# mcp23007_uln2803a.net
KiCad netlist of a schematic drawn in EAGLE
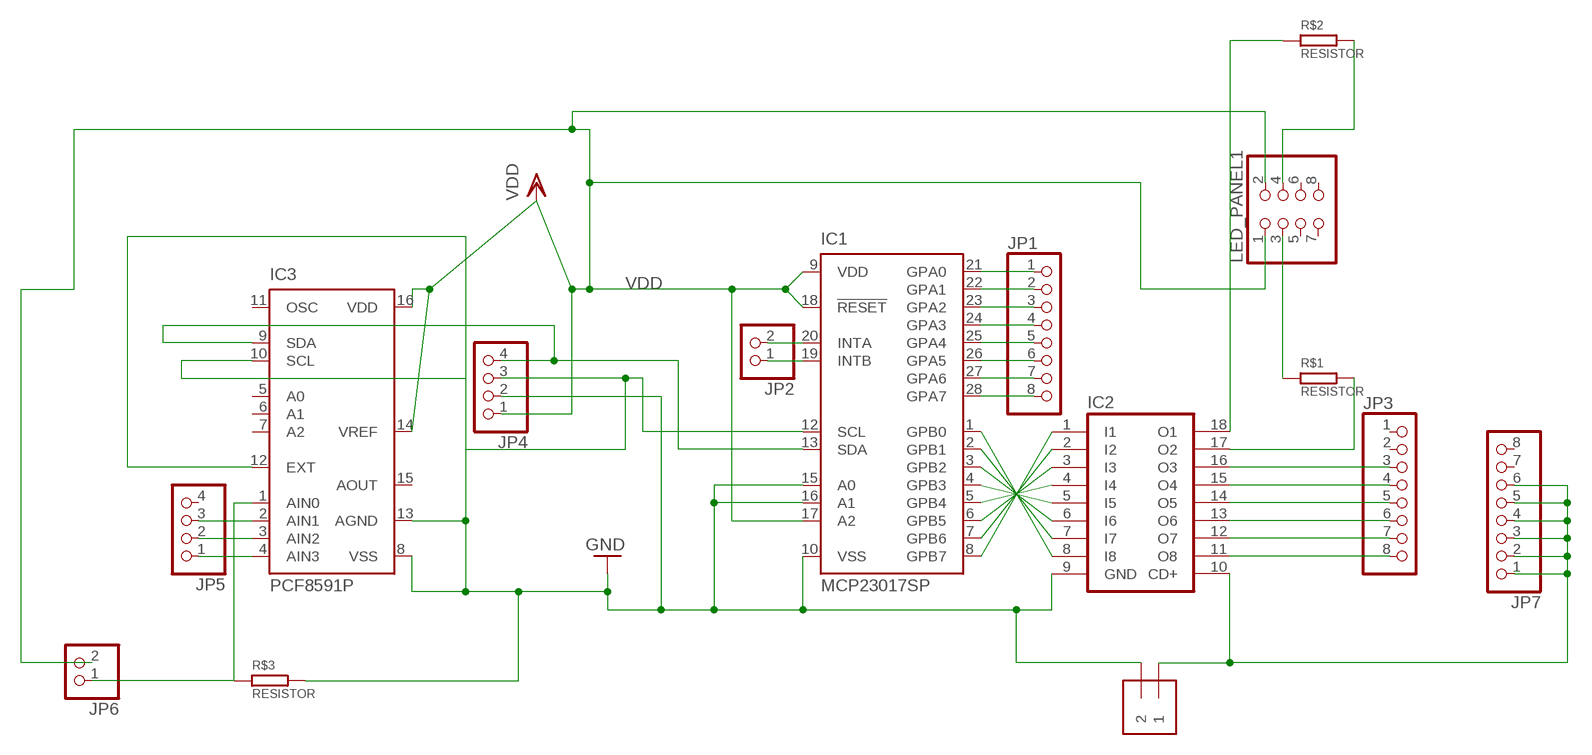
[diagram p0: schematic, sheet 1]

(export (version "E")
  (design (tool "Eeschema 10.0.6"))
  (components
    (comp (ref "IC1")
      (value "MCP23017SP")
      (footprint "eagle-import:DIL28-3")
      (fields (field (name "MF") "MICROCHIP") (field (name "MPN") "MCP23017-E/SP"))
      (libsource (lib "eagle-import") (part "MCP23017SP"))
    )
    (comp (ref "IC2")
      (value "ULN2803A")
      (footprint "eagle-import:DIL18")
      (libsource (lib "eagle-import") (part "ULN2803A"))
    )
    (comp (ref "IC3")
      (value "PCF8591P")
      (footprint "eagle-import:DIL16")
      (fields (field (name "MF") "FARNELL"))
      (libsource (lib "eagle-import") (part "PCF8591P"))
    )
    (comp (ref "JP1")
      (value "PINHD-1X8")
      (footprint "eagle-import:1X08")
      (libsource (lib "eagle-import") (part "PINHD-1X8"))
    )
    (comp (ref "JP2")
      (value "PINHD-1X2")
      (footprint "eagle-import:1X02")
      (libsource (lib "eagle-import") (part "PINHD-1X2"))
    )
    (comp (ref "JP3")
      (value "PINHD-1X8")
      (footprint "eagle-import:1X08")
      (libsource (lib "eagle-import") (part "PINHD-1X8"))
    )
    (comp (ref "JP4")
      (value "PINHD-1X4")
      (footprint "eagle-import:1X04")
      (libsource (lib "eagle-import") (part "PINHD-1X4"))
    )
    (comp (ref "JP5")
      (value "PINHD-1X4")
      (footprint "eagle-import:1X04")
      (libsource (lib "eagle-import") (part "PINHD-1X4"))
    )
    (comp (ref "JP6")
      (value "PINHD-1X2")
      (footprint "eagle-import:1X02")
      (libsource (lib "eagle-import") (part "PINHD-1X2"))
    )
    (comp (ref "JP7")
      (value "PINHD-1X8")
      (footprint "eagle-import:1X08")
      (libsource (lib "eagle-import") (part "PINHD-1X8"))
    )
    (comp (ref "LED_PANEL1")
      (value "PINHD-2X4")
      (footprint "eagle-import:2X04")
      (libsource (lib "eagle-import") (part "PINHD-2X4"))
    )
    (comp (ref "R$1")
      (value "RESISTOR")
      (footprint "eagle-import:RESISTOR_1_4")
      (libsource (lib "eagle-import") (part "RESISTOR"))
    )
    (comp (ref "R$2")
      (value "RESISTOR")
      (footprint "eagle-import:RESISTOR_1_4")
      (libsource (lib "eagle-import") (part "RESISTOR"))
    )
    (comp (ref "R$3")
      (value "RESISTOR")
      (footprint "eagle-import:RESISTOR_1_4")
      (libsource (lib "eagle-import") (part "RESISTOR"))
    )
    (comp (ref "VCC")
      (value "1X2-3.5MM")
      (footprint "eagle-import:1X2-3.5MM")
      (libsource (lib "eagle-import") (part "1X2-3.5MM"))
    )
  )
  (nets
    (net (code "1") (name "GND") (class "Default")
      (node (ref "IC1") (pin "10") (pinfunction "VSS_10") (pintype "power_in"))
      (node (ref "IC1") (pin "15") (pinfunction "A0_15") (pintype "input"))
      (node (ref "IC1") (pin "16") (pinfunction "A1_16") (pintype "input"))
      (node (ref "IC2") (pin "9") (pinfunction "GND_9") (pintype "power_in"))
      (node (ref "IC3") (pin "12") (pinfunction "EXT_12") (pintype "input"))
      (node (ref "IC3") (pin "13") (pinfunction "AGND_13") (pintype "power_in"))
      (node (ref "IC3") (pin "8") (pinfunction "VSS_8") (pintype "power_in"))
      (node (ref "JP4") (pin "2") (pinfunction "2_2") (pintype "passive"))
      (node (ref "R$3") (pin "P$1") (pinfunction "P$1_P$1") (pintype "passive"))
      (node (ref "VCC") (pin "2") (pinfunction "2_2") (pintype "passive"))
    )
    (net (code "2") (name "Net-(IC1-GPA0)") (class "Default")
      (node (ref "IC1") (pin "21") (pinfunction "GPA0_21") (pintype "bidirectional"))
      (node (ref "JP1") (pin "1") (pinfunction "1_1") (pintype "passive"))
    )
    (net (code "3") (name "Net-(IC1-GPA1)") (class "Default")
      (node (ref "IC1") (pin "22") (pinfunction "GPA1_22") (pintype "bidirectional"))
      (node (ref "JP1") (pin "2") (pinfunction "2_2") (pintype "passive"))
    )
    (net (code "4") (name "Net-(IC1-GPA2)") (class "Default")
      (node (ref "IC1") (pin "23") (pinfunction "GPA2_23") (pintype "bidirectional"))
      (node (ref "JP1") (pin "3") (pinfunction "3_3") (pintype "passive"))
    )
    (net (code "5") (name "Net-(IC1-GPA3)") (class "Default")
      (node (ref "IC1") (pin "24") (pinfunction "GPA3_24") (pintype "bidirectional"))
      (node (ref "JP1") (pin "4") (pinfunction "4_4") (pintype "passive"))
    )
    (net (code "6") (name "Net-(IC1-GPA4)") (class "Default")
      (node (ref "IC1") (pin "25") (pinfunction "GPA4_25") (pintype "bidirectional"))
      (node (ref "JP1") (pin "5") (pinfunction "5_5") (pintype "passive"))
    )
    (net (code "7") (name "Net-(IC1-GPA5)") (class "Default")
      (node (ref "IC1") (pin "26") (pinfunction "GPA5_26") (pintype "bidirectional"))
      (node (ref "JP1") (pin "6") (pinfunction "6_6") (pintype "passive"))
    )
    (net (code "8") (name "Net-(IC1-GPA6)") (class "Default")
      (node (ref "IC1") (pin "27") (pinfunction "GPA6_27") (pintype "bidirectional"))
      (node (ref "JP1") (pin "7") (pinfunction "7_7") (pintype "passive"))
    )
    (net (code "9") (name "Net-(IC1-GPA7)") (class "Default")
      (node (ref "IC1") (pin "28") (pinfunction "GPA7_28") (pintype "bidirectional"))
      (node (ref "JP1") (pin "8") (pinfunction "8_8") (pintype "passive"))
    )
    (net (code "10") (name "Net-(IC1-GPB0)") (class "Default")
      (node (ref "IC1") (pin "1") (pinfunction "GPB0_1") (pintype "bidirectional"))
      (node (ref "IC2") (pin "8") (pinfunction "I8_8") (pintype "input"))
    )
    (net (code "11") (name "Net-(IC1-GPB1)") (class "Default")
      (node (ref "IC1") (pin "2") (pinfunction "GPB1_2") (pintype "bidirectional"))
      (node (ref "IC2") (pin "7") (pinfunction "I7_7") (pintype "input"))
    )
    (net (code "12") (name "Net-(IC1-GPB2)") (class "Default")
      (node (ref "IC1") (pin "3") (pinfunction "GPB2_3") (pintype "bidirectional"))
      (node (ref "IC2") (pin "6") (pinfunction "I6_6") (pintype "input"))
    )
    (net (code "13") (name "Net-(IC1-GPB3)") (class "Default")
      (node (ref "IC1") (pin "4") (pinfunction "GPB3_4") (pintype "bidirectional"))
      (node (ref "IC2") (pin "5") (pinfunction "I5_5") (pintype "input"))
    )
    (net (code "14") (name "Net-(IC1-GPB4)") (class "Default")
      (node (ref "IC1") (pin "5") (pinfunction "GPB4_5") (pintype "bidirectional"))
      (node (ref "IC2") (pin "4") (pinfunction "I4_4") (pintype "input"))
    )
    (net (code "15") (name "Net-(IC1-GPB5)") (class "Default")
      (node (ref "IC1") (pin "6") (pinfunction "GPB5_6") (pintype "bidirectional"))
      (node (ref "IC2") (pin "3") (pinfunction "I3_3") (pintype "input"))
    )
    (net (code "16") (name "Net-(IC1-GPB6)") (class "Default")
      (node (ref "IC1") (pin "7") (pinfunction "GPB6_7") (pintype "bidirectional"))
      (node (ref "IC2") (pin "2") (pinfunction "I2_2") (pintype "input"))
    )
    (net (code "17") (name "Net-(IC1-GPB7)") (class "Default")
      (node (ref "IC1") (pin "8") (pinfunction "GPB7_8") (pintype "bidirectional"))
      (node (ref "IC2") (pin "1") (pinfunction "I1_1") (pintype "input"))
    )
    (net (code "18") (name "Net-(IC1-INTA)") (class "Default")
      (node (ref "IC1") (pin "20") (pinfunction "INTA_20") (pintype "output"))
      (node (ref "JP2") (pin "2") (pinfunction "2_2") (pintype "passive"))
    )
    (net (code "19") (name "Net-(IC1-INTB)") (class "Default")
      (node (ref "IC1") (pin "19") (pinfunction "INTB_19") (pintype "output"))
      (node (ref "JP2") (pin "1") (pinfunction "1_1") (pintype "passive"))
    )
    (net (code "20") (name "Net-(IC1-SCL)") (class "Default")
      (node (ref "IC1") (pin "12") (pinfunction "SCL_12") (pintype "input"))
      (node (ref "IC3") (pin "10") (pinfunction "SCL_10") (pintype "input"))
      (node (ref "JP4") (pin "3") (pinfunction "3_3") (pintype "passive"))
    )
    (net (code "21") (name "Net-(IC1-SDA)") (class "Default")
      (node (ref "IC1") (pin "13") (pinfunction "SDA_13") (pintype "bidirectional"))
      (node (ref "IC3") (pin "9") (pinfunction "SDA_9") (pintype "bidirectional"))
      (node (ref "JP4") (pin "4") (pinfunction "4_4") (pintype "passive"))
    )
    (net (code "22") (name "Net-(IC2-CD+)") (class "Default")
      (node (ref "IC2") (pin "10") (pinfunction "CD+_10") (pintype "passive"))
      (node (ref "JP7") (pin "1") (pinfunction "1_1") (pintype "passive"))
      (node (ref "JP7") (pin "2") (pinfunction "2_2") (pintype "passive"))
      (node (ref "JP7") (pin "3") (pinfunction "3_3") (pintype "passive"))
      (node (ref "JP7") (pin "4") (pinfunction "4_4") (pintype "passive"))
      (node (ref "JP7") (pin "5") (pinfunction "5_5") (pintype "passive"))
      (node (ref "JP7") (pin "6") (pinfunction "6_6") (pintype "passive"))
      (node (ref "VCC") (pin "1") (pinfunction "1_1") (pintype "passive"))
    )
    (net (code "23") (name "Net-(IC2-O1)") (class "Default")
      (node (ref "IC2") (pin "18") (pinfunction "O1_18") (pintype "open_collector"))
      (node (ref "R$2") (pin "P$2") (pinfunction "P$2_P$2") (pintype "passive"))
    )
    (net (code "24") (name "Net-(IC2-O2)") (class "Default")
      (node (ref "IC2") (pin "17") (pinfunction "O2_17") (pintype "open_collector"))
      (node (ref "R$1") (pin "P$1") (pinfunction "P$1_P$1") (pintype "passive"))
    )
    (net (code "25") (name "Net-(IC2-O3)") (class "Default")
      (node (ref "IC2") (pin "16") (pinfunction "O3_16") (pintype "open_collector"))
      (node (ref "JP3") (pin "3") (pinfunction "3_3") (pintype "passive"))
    )
    (net (code "26") (name "Net-(IC2-O4)") (class "Default")
      (node (ref "IC2") (pin "15") (pinfunction "O4_15") (pintype "open_collector"))
      (node (ref "JP3") (pin "4") (pinfunction "4_4") (pintype "passive"))
    )
    (net (code "27") (name "Net-(IC2-O5)") (class "Default")
      (node (ref "IC2") (pin "14") (pinfunction "O5_14") (pintype "open_collector"))
      (node (ref "JP3") (pin "5") (pinfunction "5_5") (pintype "passive"))
    )
    (net (code "28") (name "Net-(IC2-O6)") (class "Default")
      (node (ref "IC2") (pin "13") (pinfunction "O6_13") (pintype "open_collector"))
      (node (ref "JP3") (pin "6") (pinfunction "6_6") (pintype "passive"))
    )
    (net (code "29") (name "Net-(IC2-O7)") (class "Default")
      (node (ref "IC2") (pin "12") (pinfunction "O7_12") (pintype "open_collector"))
      (node (ref "JP3") (pin "7") (pinfunction "7_7") (pintype "passive"))
    )
    (net (code "30") (name "Net-(IC2-O8)") (class "Default")
      (node (ref "IC2") (pin "11") (pinfunction "O8_11") (pintype "open_collector"))
      (node (ref "JP3") (pin "8") (pinfunction "8_8") (pintype "passive"))
    )
    (net (code "31") (name "Net-(IC3-AIN0)") (class "Default")
      (node (ref "IC3") (pin "1") (pinfunction "AIN0_1") (pintype "input"))
      (node (ref "JP6") (pin "1") (pinfunction "1_1") (pintype "passive"))
      (node (ref "R$3") (pin "P$2") (pinfunction "P$2_P$2") (pintype "passive"))
    )
    (net (code "32") (name "Net-(IC3-AIN1)") (class "Default")
      (node (ref "IC3") (pin "2") (pinfunction "AIN1_2") (pintype "input"))
      (node (ref "JP5") (pin "3") (pinfunction "3_3") (pintype "passive"))
    )
    (net (code "33") (name "Net-(IC3-AIN2)") (class "Default")
      (node (ref "IC3") (pin "3") (pinfunction "AIN2_3") (pintype "input"))
      (node (ref "JP5") (pin "2") (pinfunction "2_2") (pintype "passive"))
    )
    (net (code "34") (name "Net-(IC3-AIN3)") (class "Default")
      (node (ref "IC3") (pin "4") (pinfunction "AIN3_4") (pintype "input"))
      (node (ref "JP5") (pin "1") (pinfunction "1_1") (pintype "passive"))
    )
    (net (code "35") (name "Net-(LED_PANEL1-Pad3)") (class "Default")
      (node (ref "LED_PANEL1") (pin "3") (pinfunction "3_3") (pintype "passive"))
      (node (ref "R$1") (pin "P$2") (pinfunction "P$2_P$2") (pintype "passive"))
    )
    (net (code "36") (name "Net-(LED_PANEL1-Pad4)") (class "Default")
      (node (ref "LED_PANEL1") (pin "4") (pinfunction "4_4") (pintype "passive"))
      (node (ref "R$2") (pin "P$1") (pinfunction "P$1_P$1") (pintype "passive"))
    )
    (net (code "37") (name "VDD") (class "Default")
      (node (ref "IC1") (pin "17") (pinfunction "A2_17") (pintype "input"))
      (node (ref "IC1") (pin "18") (pinfunction "~{RESET}_18") (pintype "input"))
      (node (ref "IC1") (pin "9") (pinfunction "VDD_9") (pintype "power_in"))
      (node (ref "IC3") (pin "14") (pinfunction "VREF_14") (pintype "input"))
      (node (ref "IC3") (pin "16") (pinfunction "VDD_16") (pintype "power_in"))
      (node (ref "JP4") (pin "1") (pinfunction "1_1") (pintype "passive"))
      (node (ref "JP6") (pin "2") (pinfunction "2_2") (pintype "passive"))
      (node (ref "LED_PANEL1") (pin "1") (pinfunction "1_1") (pintype "passive"))
      (node (ref "LED_PANEL1") (pin "2") (pinfunction "2_2") (pintype "passive"))
    )
    (net (code "38") (name "unconnected-(IC3-A0-Pad5)") (class "Default")
      (node (ref "IC3") (pin "5") (pinfunction "A0_5") (pintype "input"))
    )
    (net (code "39") (name "unconnected-(IC3-A1-Pad6)") (class "Default")
      (node (ref "IC3") (pin "6") (pinfunction "A1_6") (pintype "input"))
    )
    (net (code "40") (name "unconnected-(IC3-A2-Pad7)") (class "Default")
      (node (ref "IC3") (pin "7") (pinfunction "A2_7") (pintype "input"))
    )
    (net (code "41") (name "unconnected-(IC3-AOUT-Pad15)") (class "Default")
      (node (ref "IC3") (pin "15") (pinfunction "AOUT_15") (pintype "output"))
    )
    (net (code "42") (name "unconnected-(IC3-OSC-Pad11)") (class "Default")
      (node (ref "IC3") (pin "11") (pinfunction "OSC_11") (pintype "input"))
    )
    (net (code "43") (name "unconnected-(JP3-Pad1)") (class "Default")
      (node (ref "JP3") (pin "1") (pinfunction "1_1") (pintype "passive"))
    )
    (net (code "44") (name "unconnected-(JP3-Pad2)") (class "Default")
      (node (ref "JP3") (pin "2") (pinfunction "2_2") (pintype "passive"))
    )
    (net (code "45") (name "unconnected-(JP5-Pad4)") (class "Default")
      (node (ref "JP5") (pin "4") (pinfunction "4_4") (pintype "passive"))
    )
    (net (code "46") (name "unconnected-(JP7-Pad7)") (class "Default")
      (node (ref "JP7") (pin "7") (pinfunction "7_7") (pintype "passive"))
    )
    (net (code "47") (name "unconnected-(JP7-Pad8)") (class "Default")
      (node (ref "JP7") (pin "8") (pinfunction "8_8") (pintype "passive"))
    )
    (net (code "48") (name "unconnected-(LED_PANEL1-Pad5)") (class "Default")
      (node (ref "LED_PANEL1") (pin "5") (pinfunction "5_5") (pintype "passive"))
    )
    (net (code "49") (name "unconnected-(LED_PANEL1-Pad6)") (class "Default")
      (node (ref "LED_PANEL1") (pin "6") (pinfunction "6_6") (pintype "passive"))
    )
    (net (code "50") (name "unconnected-(LED_PANEL1-Pad7)") (class "Default")
      (node (ref "LED_PANEL1") (pin "7") (pinfunction "7_7") (pintype "passive"))
    )
    (net (code "51") (name "unconnected-(LED_PANEL1-Pad8)") (class "Default")
      (node (ref "LED_PANEL1") (pin "8") (pinfunction "8_8") (pintype "passive"))
    )
  )
)
